# NVME.net
KiCad netlist of a schematic drawn in Altium Designer
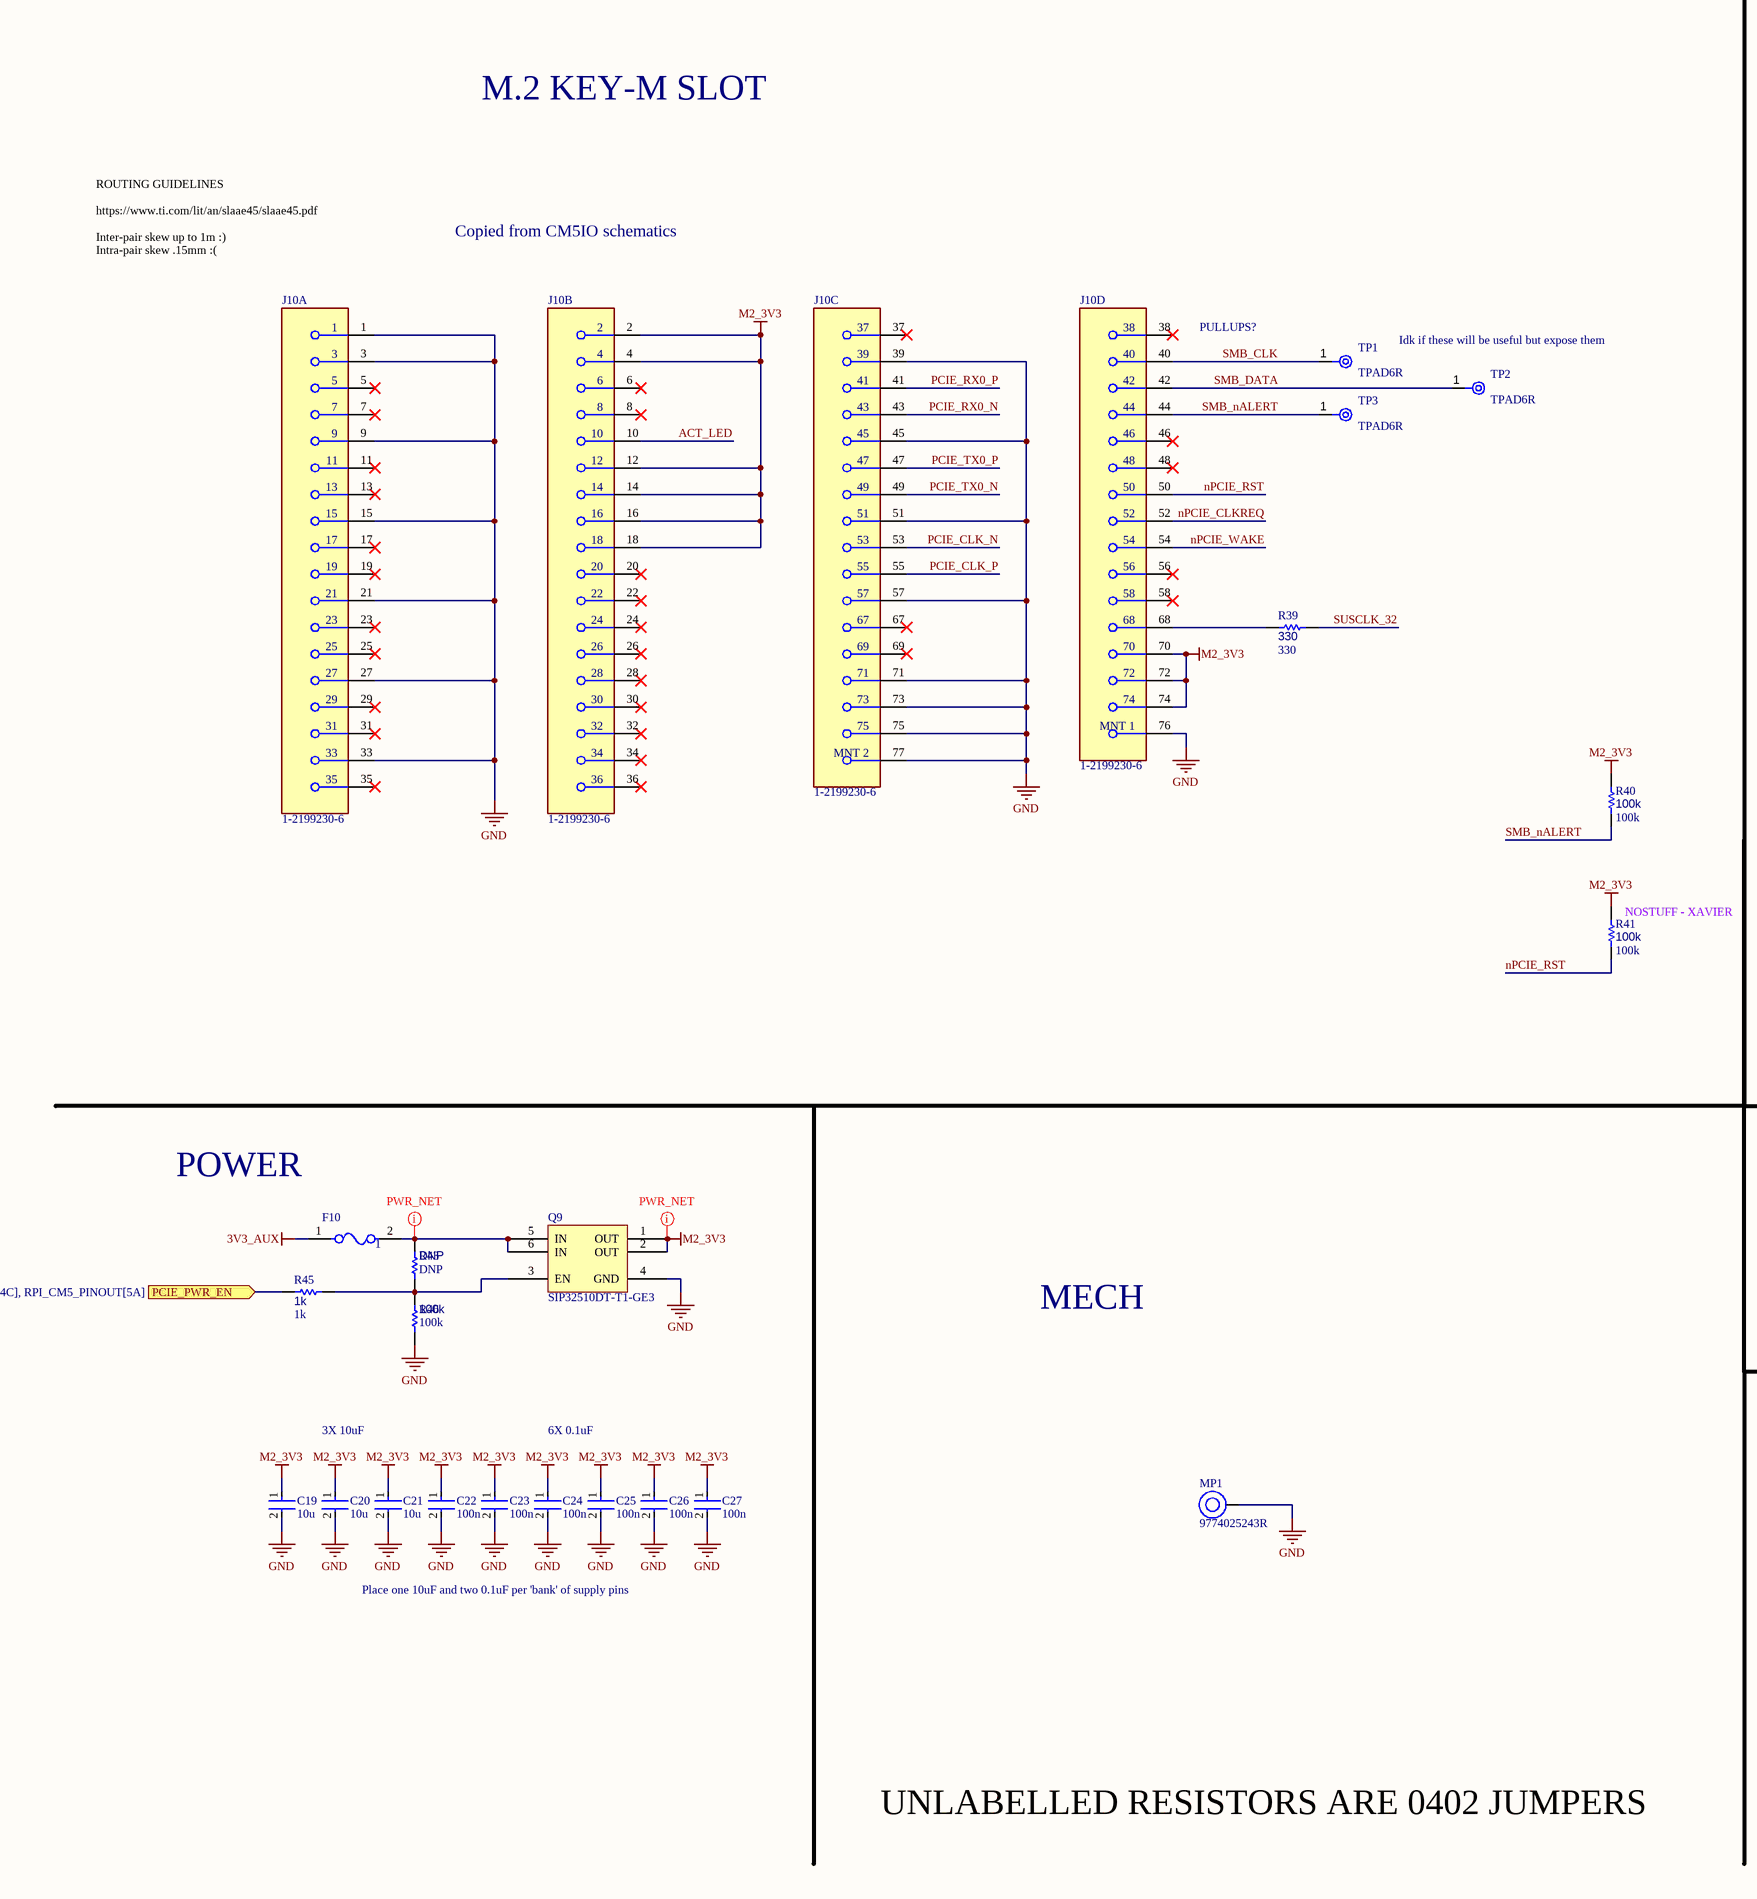
[diagram p0: NVME.SchDoc, left]
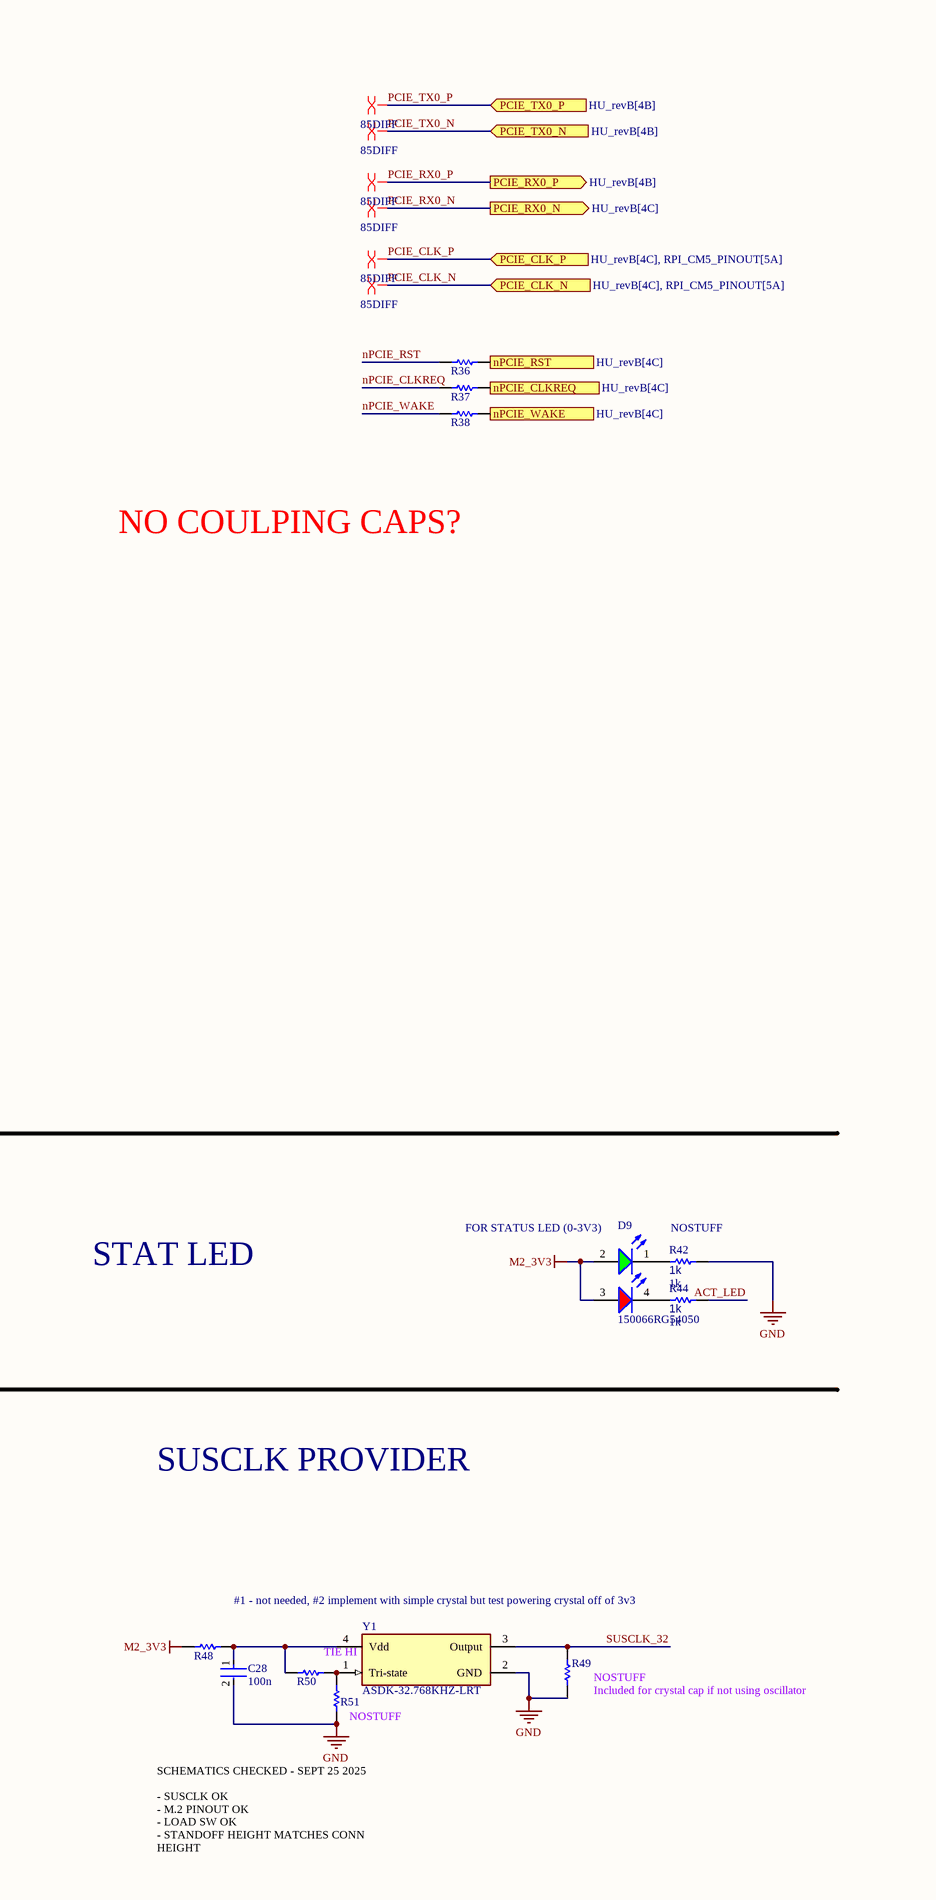
[diagram p1: NVME.SchDoc, right]

(export (version "E")
  (design (tool "Eeschema 10.0.6"))
  (components
    (comp (ref "C19")
      (value "10u")
      (footprint "FP-0402-L_1_0_0_05-W_0_5-IPC_A")
      (description "LARGE PADS, 0402 CAP, CHANGE COMMENT TO MATCH REAL P/N")
      (libsource (lib "Space Concordia") (part "b4654b650e69147ec39a6b967a45e02"))
    )
    (comp (ref "C20")
      (value "10u")
      (footprint "FP-0402-L_1_0_0_05-W_0_5-IPC_A")
      (description "LARGE PADS, 0402 CAP, CHANGE COMMENT TO MATCH REAL P/N")
      (libsource (lib "Space Concordia") (part "b4654b650e69147ec39a6b967a45e02"))
    )
    (comp (ref "C21")
      (value "10u")
      (footprint "FP-0402-L_1_0_0_05-W_0_5-IPC_A")
      (description "LARGE PADS, 0402 CAP, CHANGE COMMENT TO MATCH REAL P/N")
      (libsource (lib "Space Concordia") (part "b4654b650e69147ec39a6b967a45e02"))
    )
    (comp (ref "C22")
      (value "100n")
      (footprint "FP-0402-L_1_0_0_05-W_0_5-IPC_A")
      (description "LARGE PADS, 0402 CAP, CHANGE COMMENT TO MATCH REAL P/N")
      (libsource (lib "Space Concordia") (part "b4654b650e69147ec39a6b967a45e02"))
    )
    (comp (ref "C23")
      (value "100n")
      (footprint "FP-0402-L_1_0_0_05-W_0_5-IPC_A")
      (description "LARGE PADS, 0402 CAP, CHANGE COMMENT TO MATCH REAL P/N")
      (libsource (lib "Space Concordia") (part "b4654b650e69147ec39a6b967a45e02"))
    )
    (comp (ref "C24")
      (value "100n")
      (footprint "FP-0402-L_1_0_0_05-W_0_5-IPC_A")
      (description "LARGE PADS, 0402 CAP, CHANGE COMMENT TO MATCH REAL P/N")
      (libsource (lib "Space Concordia") (part "b4654b650e69147ec39a6b967a45e02"))
    )
    (comp (ref "C25")
      (value "100n")
      (footprint "FP-0402-L_1_0_0_05-W_0_5-IPC_A")
      (description "LARGE PADS, 0402 CAP, CHANGE COMMENT TO MATCH REAL P/N")
      (libsource (lib "Space Concordia") (part "b4654b650e69147ec39a6b967a45e02"))
    )
    (comp (ref "C26")
      (value "100n")
      (footprint "FP-0402-L_1_0_0_05-W_0_5-IPC_A")
      (description "LARGE PADS, 0402 CAP, CHANGE COMMENT TO MATCH REAL P/N")
      (libsource (lib "Space Concordia") (part "b4654b650e69147ec39a6b967a45e02"))
    )
    (comp (ref "C27")
      (value "100n")
      (footprint "FP-0402-L_1_0_0_05-W_0_5-IPC_A")
      (description "LARGE PADS, 0402 CAP, CHANGE COMMENT TO MATCH REAL P/N")
      (libsource (lib "Space Concordia") (part "b4654b650e69147ec39a6b967a45e02"))
    )
    (comp (ref "C28")
      (value "100n")
      (footprint "FP-0402-L_1_0_0_05-W_0_5-IPC_A")
      (description "LARGE PADS, 0402 CAP, CHANGE COMMENT TO MATCH REAL P/N")
      (libsource (lib "Space Concordia") (part "b4654b650e69147ec39a6b967a45e02"))
    )
    (comp (ref "D9")
      (value "150066RG54050")
      (footprint "WL-SBCD_0606")
      (description "Led, Red/Grn, 180Mcd/230Mcd, 624Nm/525Nm Rohs Compliant: Yes")
      (fields (field (name "SOURCE") "rgled.SchLib"))
      (libsource (lib "Space Concordia") (part "CMP-004-00034-2"))
    )
    (comp (ref "F10")
      (value "1")
      (footprint "FP-0685T-MFG")
      (description "FUSE BOARD MNT 5A 63VAC/VDC 1206")
      (libsource (lib "Altium Content Vault") (part "5bcf9b9f640e542cf0359d10258e979"))
    )
    (comp (ref "J10")
      (value "1-2199230-6")
      (footprint "FP-1-2199230-6-MFG")
      (description "CONN EDGE DUAL FMALE 67POS 0.020")
      (fields
        (field (name "MANUFACTURER") "TE")
        (field (name "OCTOPART") "https://octopart.com/1-2199230-6-te+connectivity-34969376")
      )
      (libsource (lib "Altium Content Vault") (part "bdc5cd39fb5e3adfc3cf7d042564072"))
    )
    (comp (ref "MP1")
      (value "9774025243R")
      (footprint "9774025243")
      (description "9774025243R Spacer Material: Steel, Tin-Plated Mounting: SMT Series: WA-SMST Thread D: M2")
      (libsource (lib "Altium Content Vault") (part "Spacer"))
    )
    (comp (ref "Q9")
      (value "SIP32510DT-T1-GE3")
      (footprint "SOT95P284X110-6N")
      (description "Power Switch ICs – Power Distribution; VISHAY; SIP32510DT-T1-GE3; 1; 1; 5.5 V; SOT-23-6")
      (libsource (lib "Space Concordia") (part "SIP32510DT-T1-GE3"))
    )
    (comp (ref "R36")
      (value "0402 JUMPER")
      (footprint "RESC1005X40X25ML05T05")
      (description "READ THE NAME")
      (libsource (lib "Space Concordia") (part "CMP-009-00206-2"))
    )
    (comp (ref "R37")
      (value "0402 JUMPER")
      (footprint "RESC1005X40X25ML05T05")
      (description "READ THE NAME")
      (libsource (lib "Space Concordia") (part "CMP-009-00206-2"))
    )
    (comp (ref "R38")
      (value "0402 JUMPER")
      (footprint "RESC1005X40X25ML05T05")
      (description "READ THE NAME")
      (libsource (lib "Space Concordia") (part "CMP-009-00206-2"))
    )
    (comp (ref "R39")
      (value "330")
      (footprint "R0603B")
      (description "Resistor")
      (fields (field (name "ALTIUM_VALUE") "330"))
      (libsource (lib "Space Concordia") (part "Resistor"))
    )
    (comp (ref "R40")
      (value "100k")
      (footprint "R0603B")
      (description "Resistor")
      (fields (field (name "ALTIUM_VALUE") "100k"))
      (libsource (lib "Space Concordia") (part "Resistor"))
    )
    (comp (ref "R41")
      (value "100k")
      (footprint "R0603B")
      (description "Resistor")
      (fields (field (name "ALTIUM_VALUE") "100k"))
      (libsource (lib "Space Concordia") (part "Resistor"))
    )
    (comp (ref "R42")
      (value "1k")
      (footprint "R0603B")
      (description "Resistor")
      (fields (field (name "ALTIUM_VALUE") "1k"))
      (libsource (lib "Space Concordia") (part "Resistor"))
    )
    (comp (ref "R43")
      (value "DNP")
      (footprint "R0603B")
      (description "Resistor")
      (fields (field (name "ALTIUM_VALUE") "DNP"))
      (libsource (lib "Space Concordia") (part "Resistor"))
    )
    (comp (ref "R44")
      (value "1k")
      (footprint "R0603B")
      (description "Resistor")
      (fields (field (name "ALTIUM_VALUE") "1k"))
      (libsource (lib "Space Concordia") (part "Resistor"))
    )
    (comp (ref "R45")
      (value "1k")
      (footprint "R0603B")
      (description "Resistor")
      (fields (field (name "ALTIUM_VALUE") "1k"))
      (libsource (lib "Space Concordia") (part "Resistor"))
    )
    (comp (ref "R46")
      (value "100k")
      (footprint "R0603B")
      (description "Resistor")
      (fields (field (name "ALTIUM_VALUE") "100k"))
      (libsource (lib "Space Concordia") (part "Resistor"))
    )
    (comp (ref "R48")
      (value "0402 JUMPER")
      (footprint "RESC1005X40X25ML05T05")
      (description "READ THE NAME")
      (libsource (lib "Space Concordia") (part "CMP-009-00206-2"))
    )
    (comp (ref "R49")
      (value "0402 JUMPER")
      (footprint "RESC1005X40X25ML05T05")
      (description "READ THE NAME")
      (libsource (lib "Space Concordia") (part "CMP-009-00206-2"))
    )
    (comp (ref "R50")
      (value "0402 JUMPER")
      (footprint "RESC1005X40X25ML05T05")
      (description "READ THE NAME")
      (libsource (lib "Space Concordia") (part "CMP-009-00206-2"))
    )
    (comp (ref "R51")
      (value "0402 JUMPER")
      (footprint "RESC1005X40X25ML05T05")
      (description "READ THE NAME")
      (libsource (lib "Space Concordia") (part "CMP-009-00206-2"))
    )
    (comp (ref "TP1")
      (value "TPAD6R")
      (footprint "New footprint 1")
      (description "Test Point .6mm")
      (libsource (lib "Space Concordia") (part "TP"))
    )
    (comp (ref "TP2")
      (value "TPAD6R")
      (footprint "New footprint 1")
      (description "Test Point .6mm")
      (libsource (lib "Space Concordia") (part "TP"))
    )
    (comp (ref "TP3")
      (value "TPAD6R")
      (footprint "New footprint 1")
      (description "Test Point .6mm")
      (libsource (lib "Space Concordia") (part "TP"))
    )
    (comp (ref "Y1")
      (value "ASDK-32.768KHZ-LRT")
      (footprint "FP-ASDK-MFG")
      (description "XTAL OSC XO 32.7680KHZ CMOS SMD")
      (libsource (lib "Altium Content Vault") (part "a7425352bb6ebc83bfd0f12a23808e7"))
    )
  )
  (nets
    (net (code "1") (name "/ACT_LED") (class "Default")
      (node (ref "J10") (pin "10") (pinfunction "10_10") (pintype "passive"))
      (node (ref "R44") (pin "2") (pinfunction "2_2") (pintype "passive"))
    )
    (net (code "2") (name "/PCIE_CLK_N") (class "Default")
      (node (ref "J10") (pin "53") (pinfunction "53_53") (pintype "passive"))
    )
    (net (code "3") (name "/PCIE_CLK_P") (class "Default")
      (node (ref "J10") (pin "55") (pinfunction "55_55") (pintype "passive"))
    )
    (net (code "4") (name "/PCIE_PWR_EN") (class "Default")
      (node (ref "R45") (pin "2") (pinfunction "2_2") (pintype "passive"))
    )
    (net (code "5") (name "/PCIE_RX0_N") (class "Default")
      (node (ref "J10") (pin "43") (pinfunction "43_43") (pintype "passive"))
    )
    (net (code "6") (name "/PCIE_RX0_P") (class "Default")
      (node (ref "J10") (pin "41") (pinfunction "41_41") (pintype "passive"))
    )
    (net (code "7") (name "/PCIE_TX0_N") (class "Default")
      (node (ref "J10") (pin "49") (pinfunction "49_49") (pintype "passive"))
    )
    (net (code "8") (name "/PCIE_TX0_P") (class "Default")
      (node (ref "J10") (pin "47") (pinfunction "47_47") (pintype "passive"))
    )
    (net (code "9") (name "/SMB_CLK") (class "Default")
      (node (ref "J10") (pin "40") (pinfunction "40_40") (pintype "passive"))
      (node (ref "TP1") (pin "1") (pinfunction "TP_1") (pintype "passive"))
    )
    (net (code "10") (name "/SMB_DATA") (class "Default")
      (node (ref "J10") (pin "42") (pinfunction "42_42") (pintype "passive"))
      (node (ref "TP2") (pin "1") (pinfunction "TP_1") (pintype "passive"))
    )
    (net (code "11") (name "/SMB_nALERT") (class "Default")
      (node (ref "J10") (pin "44") (pinfunction "44_44") (pintype "passive"))
      (node (ref "R40") (pin "2") (pinfunction "2_2") (pintype "passive"))
      (node (ref "TP3") (pin "1") (pinfunction "TP_1") (pintype "passive"))
    )
    (net (code "12") (name "/SUSCLK_32") (class "Default")
      (node (ref "R39") (pin "1") (pinfunction "1_1") (pintype "passive"))
      (node (ref "R49") (pin "2") (pinfunction "2_2") (pintype "passive"))
      (node (ref "Y1") (pin "3") (pinfunction "Output_3") (pintype "tri_state"))
    )
    (net (code "13") (name "/nPCIE_CLKREQ") (class "Default")
      (node (ref "J10") (pin "52") (pinfunction "52_52") (pintype "passive"))
      (node (ref "R37") (pin "1") (pinfunction "1_1") (pintype "passive"))
    )
    (net (code "14") (name "/nPCIE_RST") (class "Default")
      (node (ref "J10") (pin "50") (pinfunction "50_50") (pintype "passive"))
      (node (ref "R36") (pin "1") (pinfunction "1_1") (pintype "passive"))
      (node (ref "R41") (pin "2") (pinfunction "2_2") (pintype "passive"))
    )
    (net (code "15") (name "/nPCIE_WAKE") (class "Default")
      (node (ref "J10") (pin "54") (pinfunction "54_54") (pintype "passive"))
      (node (ref "R38") (pin "1") (pinfunction "1_1") (pintype "passive"))
    )
    (net (code "16") (name "3V3_AUX") (class "Default")
      (node (ref "F10") (pin "1") (pinfunction "1_1") (pintype "passive"))
    )
    (net (code "17") (name "GND") (class "Default")
      (node (ref "C19") (pin "2") (pinfunction "2_2") (pintype "passive"))
      (node (ref "C20") (pin "2") (pinfunction "2_2") (pintype "passive"))
      (node (ref "C21") (pin "2") (pinfunction "2_2") (pintype "passive"))
      (node (ref "C22") (pin "2") (pinfunction "2_2") (pintype "passive"))
      (node (ref "C23") (pin "2") (pinfunction "2_2") (pintype "passive"))
      (node (ref "C24") (pin "2") (pinfunction "2_2") (pintype "passive"))
      (node (ref "C25") (pin "2") (pinfunction "2_2") (pintype "passive"))
      (node (ref "C26") (pin "2") (pinfunction "2_2") (pintype "passive"))
      (node (ref "C27") (pin "2") (pinfunction "2_2") (pintype "passive"))
      (node (ref "C28") (pin "2") (pinfunction "2_2") (pintype "passive"))
      (node (ref "J10") (pin "1") (pinfunction "1_1") (pintype "passive"))
      (node (ref "J10") (pin "15") (pinfunction "15_15") (pintype "passive"))
      (node (ref "J10") (pin "21") (pinfunction "21_21") (pintype "passive"))
      (node (ref "J10") (pin "27") (pinfunction "27_27") (pintype "passive"))
      (node (ref "J10") (pin "3") (pinfunction "3_3") (pintype "passive"))
      (node (ref "J10") (pin "33") (pinfunction "33_33") (pintype "passive"))
      (node (ref "J10") (pin "39") (pinfunction "39_39") (pintype "passive"))
      (node (ref "J10") (pin "45") (pinfunction "45_45") (pintype "passive"))
      (node (ref "J10") (pin "51") (pinfunction "51_51") (pintype "passive"))
      (node (ref "J10") (pin "57") (pinfunction "57_57") (pintype "passive"))
      (node (ref "J10") (pin "71") (pinfunction "71_71") (pintype "passive"))
      (node (ref "J10") (pin "73") (pinfunction "73_73") (pintype "passive"))
      (node (ref "J10") (pin "75") (pinfunction "75_75") (pintype "passive"))
      (node (ref "J10") (pin "76") (pinfunction "MNT_1_76") (pintype "passive"))
      (node (ref "J10") (pin "77") (pinfunction "MNT_2_77") (pintype "passive"))
      (node (ref "J10") (pin "9") (pinfunction "9_9") (pintype "passive"))
      (node (ref "MP1") (pin "1") (pinfunction "1_1") (pintype "passive"))
      (node (ref "Q9") (pin "4") (pinfunction "GND_4") (pintype "passive"))
      (node (ref "R42") (pin "2") (pinfunction "2_2") (pintype "passive"))
      (node (ref "R46") (pin "1") (pinfunction "1_1") (pintype "passive"))
      (node (ref "R49") (pin "1") (pinfunction "1_1") (pintype "passive"))
      (node (ref "R51") (pin "1") (pinfunction "1_1") (pintype "passive"))
      (node (ref "Y1") (pin "2") (pinfunction "GND_2") (pintype "power_in"))
    )
    (net (code "18") (name "M2_3V3") (class "Default")
      (node (ref "C19") (pin "1") (pinfunction "1_1") (pintype "passive"))
      (node (ref "C20") (pin "1") (pinfunction "1_1") (pintype "passive"))
      (node (ref "C21") (pin "1") (pinfunction "1_1") (pintype "passive"))
      (node (ref "C22") (pin "1") (pinfunction "1_1") (pintype "passive"))
      (node (ref "C23") (pin "1") (pinfunction "1_1") (pintype "passive"))
      (node (ref "C24") (pin "1") (pinfunction "1_1") (pintype "passive"))
      (node (ref "C25") (pin "1") (pinfunction "1_1") (pintype "passive"))
      (node (ref "C26") (pin "1") (pinfunction "1_1") (pintype "passive"))
      (node (ref "C27") (pin "1") (pinfunction "1_1") (pintype "passive"))
      (node (ref "D9") (pin "2") (pinfunction "A_2") (pintype "passive"))
      (node (ref "D9") (pin "3") (pinfunction "A_3") (pintype "passive"))
      (node (ref "J10") (pin "12") (pinfunction "12_12") (pintype "passive"))
      (node (ref "J10") (pin "14") (pinfunction "14_14") (pintype "passive"))
      (node (ref "J10") (pin "16") (pinfunction "16_16") (pintype "passive"))
      (node (ref "J10") (pin "18") (pinfunction "18_18") (pintype "passive"))
      (node (ref "J10") (pin "2") (pinfunction "2_2") (pintype "passive"))
      (node (ref "J10") (pin "4") (pinfunction "4_4") (pintype "passive"))
      (node (ref "J10") (pin "70") (pinfunction "70_70") (pintype "passive"))
      (node (ref "J10") (pin "72") (pinfunction "72_72") (pintype "passive"))
      (node (ref "J10") (pin "74") (pinfunction "74_74") (pintype "passive"))
      (node (ref "Q9") (pin "1") (pinfunction "OUT_1") (pintype "passive"))
      (node (ref "Q9") (pin "2") (pinfunction "OUT_2") (pintype "passive"))
      (node (ref "R40") (pin "1") (pinfunction "1_1") (pintype "passive"))
      (node (ref "R41") (pin "1") (pinfunction "1_1") (pintype "passive"))
      (node (ref "R48") (pin "1") (pinfunction "1_1") (pintype "passive"))
    )
    (net (code "19") (name "Net-(D9-K-Pad1)") (class "Default")
      (node (ref "D9") (pin "1") (pinfunction "K_1") (pintype "passive"))
      (node (ref "R42") (pin "1") (pinfunction "1_1") (pintype "passive"))
    )
    (net (code "20") (name "Net-(D9-K-Pad4)") (class "Default")
      (node (ref "D9") (pin "4") (pinfunction "K_4") (pintype "passive"))
      (node (ref "R44") (pin "1") (pinfunction "1_1") (pintype "passive"))
    )
    (net (code "21") (name "Net-(F10-Pad2)") (class "Default")
      (node (ref "F10") (pin "2") (pinfunction "2_2") (pintype "passive"))
      (node (ref "Q9") (pin "5") (pinfunction "IN_5") (pintype "passive"))
      (node (ref "Q9") (pin "6") (pinfunction "IN_6") (pintype "passive"))
      (node (ref "R43") (pin "2") (pinfunction "2_2") (pintype "passive"))
    )
    (net (code "22") (name "Net-(J10-Pad68)") (class "Default")
      (node (ref "J10") (pin "68") (pinfunction "68_68") (pintype "passive"))
      (node (ref "R39") (pin "2") (pinfunction "2_2") (pintype "passive"))
    )
    (net (code "23") (name "Net-(Q9-EN)") (class "Default")
      (node (ref "Q9") (pin "3") (pinfunction "EN_3") (pintype "passive"))
      (node (ref "R43") (pin "1") (pinfunction "1_1") (pintype "passive"))
      (node (ref "R45") (pin "1") (pinfunction "1_1") (pintype "passive"))
      (node (ref "R46") (pin "2") (pinfunction "2_2") (pintype "passive"))
    )
    (net (code "24") (name "Net-(Y1-Tri-state)") (class "Default")
      (node (ref "R50") (pin "2") (pinfunction "2_2") (pintype "passive"))
      (node (ref "R51") (pin "2") (pinfunction "2_2") (pintype "passive"))
      (node (ref "Y1") (pin "1") (pinfunction "Tri-state_1") (pintype "input"))
    )
    (net (code "25") (name "Net-(Y1-Vdd)") (class "Default")
      (node (ref "C28") (pin "1") (pinfunction "1_1") (pintype "passive"))
      (node (ref "R48") (pin "2") (pinfunction "2_2") (pintype "passive"))
      (node (ref "R50") (pin "1") (pinfunction "1_1") (pintype "passive"))
      (node (ref "Y1") (pin "4") (pinfunction "Vdd_4") (pintype "power_in"))
    )
    (net (code "26") (name "unconnected-(J10-Pad5)") (class "Default")
      (node (ref "J10") (pin "5") (pinfunction "5_5") (pintype "passive+no_connect"))
    )
    (net (code "27") (name "unconnected-(J10-Pad6)") (class "Default")
      (node (ref "J10") (pin "6") (pinfunction "6_6") (pintype "passive+no_connect"))
    )
    (net (code "28") (name "unconnected-(J10-Pad7)") (class "Default")
      (node (ref "J10") (pin "7") (pinfunction "7_7") (pintype "passive+no_connect"))
    )
    (net (code "29") (name "unconnected-(J10-Pad8)") (class "Default")
      (node (ref "J10") (pin "8") (pinfunction "8_8") (pintype "passive+no_connect"))
    )
    (net (code "30") (name "unconnected-(J10-Pad11)") (class "Default")
      (node (ref "J10") (pin "11") (pinfunction "11_11") (pintype "passive+no_connect"))
    )
    (net (code "31") (name "unconnected-(J10-Pad13)") (class "Default")
      (node (ref "J10") (pin "13") (pinfunction "13_13") (pintype "passive+no_connect"))
    )
    (net (code "32") (name "unconnected-(J10-Pad17)") (class "Default")
      (node (ref "J10") (pin "17") (pinfunction "17_17") (pintype "passive+no_connect"))
    )
    (net (code "33") (name "unconnected-(J10-Pad19)") (class "Default")
      (node (ref "J10") (pin "19") (pinfunction "19_19") (pintype "passive+no_connect"))
    )
    (net (code "34") (name "unconnected-(J10-Pad20)") (class "Default")
      (node (ref "J10") (pin "20") (pinfunction "20_20") (pintype "passive+no_connect"))
    )
    (net (code "35") (name "unconnected-(J10-Pad22)") (class "Default")
      (node (ref "J10") (pin "22") (pinfunction "22_22") (pintype "passive+no_connect"))
    )
    (net (code "36") (name "unconnected-(J10-Pad23)") (class "Default")
      (node (ref "J10") (pin "23") (pinfunction "23_23") (pintype "passive+no_connect"))
    )
    (net (code "37") (name "unconnected-(J10-Pad24)") (class "Default")
      (node (ref "J10") (pin "24") (pinfunction "24_24") (pintype "passive+no_connect"))
    )
    (net (code "38") (name "unconnected-(J10-Pad25)") (class "Default")
      (node (ref "J10") (pin "25") (pinfunction "25_25") (pintype "passive+no_connect"))
    )
    (net (code "39") (name "unconnected-(J10-Pad26)") (class "Default")
      (node (ref "J10") (pin "26") (pinfunction "26_26") (pintype "passive+no_connect"))
    )
    (net (code "40") (name "unconnected-(J10-Pad28)") (class "Default")
      (node (ref "J10") (pin "28") (pinfunction "28_28") (pintype "passive+no_connect"))
    )
    (net (code "41") (name "unconnected-(J10-Pad29)") (class "Default")
      (node (ref "J10") (pin "29") (pinfunction "29_29") (pintype "passive+no_connect"))
    )
    (net (code "42") (name "unconnected-(J10-Pad30)") (class "Default")
      (node (ref "J10") (pin "30") (pinfunction "30_30") (pintype "passive+no_connect"))
    )
    (net (code "43") (name "unconnected-(J10-Pad31)") (class "Default")
      (node (ref "J10") (pin "31") (pinfunction "31_31") (pintype "passive+no_connect"))
    )
    (net (code "44") (name "unconnected-(J10-Pad32)") (class "Default")
      (node (ref "J10") (pin "32") (pinfunction "32_32") (pintype "passive+no_connect"))
    )
    (net (code "45") (name "unconnected-(J10-Pad34)") (class "Default")
      (node (ref "J10") (pin "34") (pinfunction "34_34") (pintype "passive+no_connect"))
    )
    (net (code "46") (name "unconnected-(J10-Pad35)") (class "Default")
      (node (ref "J10") (pin "35") (pinfunction "35_35") (pintype "passive+no_connect"))
    )
    (net (code "47") (name "unconnected-(J10-Pad36)") (class "Default")
      (node (ref "J10") (pin "36") (pinfunction "36_36") (pintype "passive+no_connect"))
    )
    (net (code "48") (name "unconnected-(J10-Pad37)") (class "Default")
      (node (ref "J10") (pin "37") (pinfunction "37_37") (pintype "passive+no_connect"))
    )
    (net (code "49") (name "unconnected-(J10-Pad38)") (class "Default")
      (node (ref "J10") (pin "38") (pinfunction "38_38") (pintype "passive+no_connect"))
    )
    (net (code "50") (name "unconnected-(J10-Pad46)") (class "Default")
      (node (ref "J10") (pin "46") (pinfunction "46_46") (pintype "passive+no_connect"))
    )
    (net (code "51") (name "unconnected-(J10-Pad48)") (class "Default")
      (node (ref "J10") (pin "48") (pinfunction "48_48") (pintype "passive+no_connect"))
    )
    (net (code "52") (name "unconnected-(J10-Pad56)") (class "Default")
      (node (ref "J10") (pin "56") (pinfunction "56_56") (pintype "passive+no_connect"))
    )
    (net (code "53") (name "unconnected-(J10-Pad58)") (class "Default")
      (node (ref "J10") (pin "58") (pinfunction "58_58") (pintype "passive+no_connect"))
    )
    (net (code "54") (name "unconnected-(J10-Pad67)") (class "Default")
      (node (ref "J10") (pin "67") (pinfunction "67_67") (pintype "passive+no_connect"))
    )
    (net (code "55") (name "unconnected-(J10-Pad69)") (class "Default")
      (node (ref "J10") (pin "69") (pinfunction "69_69") (pintype "passive+no_connect"))
    )
    (net (code "56") (name "unconnected-(R36-Pad2)") (class "Default")
      (node (ref "R36") (pin "2") (pinfunction "2_2") (pintype "passive"))
    )
    (net (code "57") (name "unconnected-(R37-Pad2)") (class "Default")
      (node (ref "R37") (pin "2") (pinfunction "2_2") (pintype "passive"))
    )
    (net (code "58") (name "unconnected-(R38-Pad2)") (class "Default")
      (node (ref "R38") (pin "2") (pinfunction "2_2") (pintype "passive"))
    )
  )
)
